# Arduino_Smart_Home_Lock.net
KiCad netlist of a schematic drawn in EAGLE
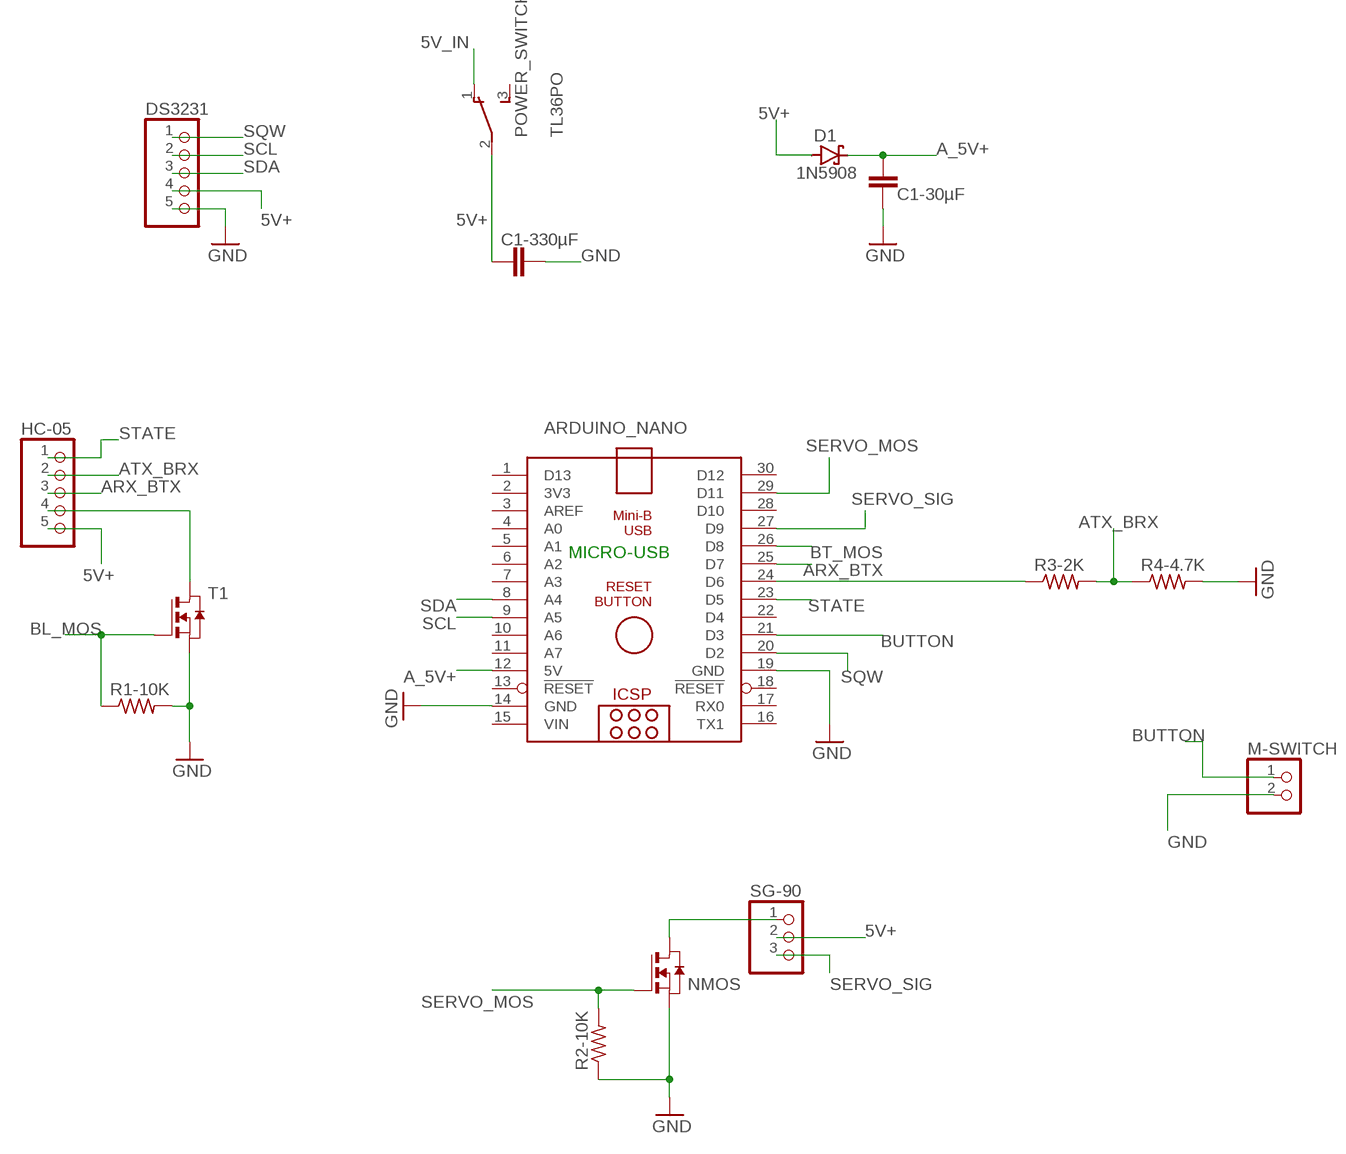
[diagram p0: schematic, sheet 1]

(export (version "E")
  (design (tool "Eeschema 10.0.6"))
  (components
    (comp (ref "ARDUINO_NANO")
      (value "ARDUINO_NANO")
      (footprint "eagle-import:ARDUINO_NANO")
      (libsource (lib "eagle-import") (part "ARDUINO_NANO"))
    )
    (comp (ref "C1-30µF")
      (value "C2.5/5")
      (footprint "eagle-import:C2.5-5")
      (libsource (lib "eagle-import") (part "C2.5/5"))
    )
    (comp (ref "C1-330µF")
      (value "C2.5/5")
      (footprint "eagle-import:C2.5-5")
      (libsource (lib "eagle-import") (part "C2.5/5"))
    )
    (comp (ref "D1")
      (value "1N5908")
      (footprint "eagle-import:C4111-15")
      (libsource (lib "eagle-import") (part "1N5908"))
    )
    (comp (ref "DS3231")
      (value "PINHD-1X55X2MM")
      (footprint "eagle-import:1_05X2MM")
      (libsource (lib "eagle-import") (part "PINHD-1X55X2MM"))
    )
    (comp (ref "HC-05")
      (value "PINHD-1X55X2MM")
      (footprint "eagle-import:1_05X2MM")
      (libsource (lib "eagle-import") (part "PINHD-1X55X2MM"))
    )
    (comp (ref "M-SWITCH")
      (value "PINHD-1X2")
      (footprint "eagle-import:1X02")
      (libsource (lib "eagle-import") (part "PINHD-1X2"))
    )
    (comp (ref "NMOS")
      (value "NMOSE3L")
      (footprint "eagle-import:E3LINE")
      (libsource (lib "eagle-import") (part "NMOSE3L"))
    )
    (comp (ref "POWER_SWITCH")
      (value "TL36PO")
      (footprint "eagle-import:TL3XPO")
      (libsource (lib "eagle-import") (part "TL36PO"))
    )
    (comp (ref "R1-10K")
      (value "R-US_0207/12")
      (footprint "eagle-import:0207_12")
      (libsource (lib "eagle-import") (part "R-US_0207/12"))
    )
    (comp (ref "R2-10K")
      (value "R-US_0207/12")
      (footprint "eagle-import:0207_12")
      (libsource (lib "eagle-import") (part "R-US_0207/12"))
    )
    (comp (ref "R3-2K")
      (value "R-US_0207/12")
      (footprint "eagle-import:0207_12")
      (libsource (lib "eagle-import") (part "R-US_0207/12"))
    )
    (comp (ref "R4-4.7K")
      (value "R-US_0207/12")
      (footprint "eagle-import:0207_12")
      (libsource (lib "eagle-import") (part "R-US_0207/12"))
    )
    (comp (ref "SG-90")
      (value "PINHD-1X3")
      (footprint "eagle-import:1X03")
      (libsource (lib "eagle-import") (part "PINHD-1X3"))
    )
    (comp (ref "T1")
      (value "NMOSE3L")
      (footprint "eagle-import:E3LINE")
      (libsource (lib "eagle-import") (part "NMOSE3L"))
    )
  )
  (nets
    (net (code "1") (name "/5V+") (class "Default")
      (node (ref "C1-330µF") (pin "1") (pinfunction "1_1") (pintype "passive"))
      (node (ref "D1") (pin "A") (pinfunction "A_A") (pintype "passive"))
      (node (ref "DS3231") (pin "4") (pinfunction "4_4") (pintype "passive"))
      (node (ref "HC-05") (pin "5") (pinfunction "5_5") (pintype "passive"))
      (node (ref "POWER_SWITCH") (pin "2") (pinfunction "P_2") (pintype "passive"))
      (node (ref "SG-90") (pin "2") (pinfunction "2_2") (pintype "passive"))
    )
    (net (code "2") (name "/5V_IN") (class "Default")
      (node (ref "POWER_SWITCH") (pin "1") (pinfunction "O_1") (pintype "passive"))
    )
    (net (code "3") (name "/ARX_BTX") (class "Default")
      (node (ref "ARDUINO_NANO") (pin "25") (pinfunction "D7_25") (pintype "bidirectional"))
      (node (ref "HC-05") (pin "3") (pinfunction "3_3") (pintype "passive"))
    )
    (net (code "4") (name "/ATX_BRX") (class "Default")
      (node (ref "HC-05") (pin "2") (pinfunction "2_2") (pintype "passive"))
      (node (ref "R3-2K") (pin "2") (pinfunction "2_2") (pintype "passive"))
      (node (ref "R4-4.7K") (pin "1") (pinfunction "1_1") (pintype "passive"))
    )
    (net (code "5") (name "/A_5V+") (class "Default")
      (node (ref "ARDUINO_NANO") (pin "12") (pinfunction "5V_12") (pintype "power_in"))
      (node (ref "C1-30µF") (pin "1") (pinfunction "1_1") (pintype "passive"))
      (node (ref "D1") (pin "C") (pinfunction "C_C") (pintype "passive"))
    )
    (net (code "6") (name "/BL_MOS") (class "Default")
      (node (ref "R1-10K") (pin "1") (pinfunction "1_1") (pintype "passive"))
      (node (ref "T1") (pin "2") (pinfunction "G_2") (pintype "passive"))
    )
    (net (code "7") (name "/BT_MOS") (class "Default")
      (node (ref "ARDUINO_NANO") (pin "26") (pinfunction "D8_26") (pintype "bidirectional"))
    )
    (net (code "8") (name "/BUTTON") (class "Default")
      (node (ref "ARDUINO_NANO") (pin "21") (pinfunction "D3_21") (pintype "bidirectional"))
      (node (ref "M-SWITCH") (pin "1") (pinfunction "1_1") (pintype "passive"))
    )
    (net (code "9") (name "/SCL") (class "Default")
      (node (ref "ARDUINO_NANO") (pin "9") (pinfunction "A5_9") (pintype "bidirectional"))
      (node (ref "DS3231") (pin "2") (pinfunction "2_2") (pintype "passive"))
    )
    (net (code "10") (name "/SDA") (class "Default")
      (node (ref "ARDUINO_NANO") (pin "8") (pinfunction "A4_8") (pintype "bidirectional"))
      (node (ref "DS3231") (pin "3") (pinfunction "3_3") (pintype "passive"))
    )
    (net (code "11") (name "/SERVO_MOS") (class "Default")
      (node (ref "ARDUINO_NANO") (pin "29") (pinfunction "D11_29") (pintype "bidirectional"))
      (node (ref "NMOS") (pin "2") (pinfunction "G_2") (pintype "passive"))
      (node (ref "R2-10K") (pin "2") (pinfunction "2_2") (pintype "passive"))
    )
    (net (code "12") (name "/SERVO_SIG") (class "Default")
      (node (ref "ARDUINO_NANO") (pin "27") (pinfunction "D9_27") (pintype "bidirectional"))
      (node (ref "SG-90") (pin "3") (pinfunction "3_3") (pintype "passive"))
    )
    (net (code "13") (name "/SQW") (class "Default")
      (node (ref "ARDUINO_NANO") (pin "20") (pinfunction "D2_20") (pintype "bidirectional"))
      (node (ref "DS3231") (pin "1") (pinfunction "1_1") (pintype "passive"))
    )
    (net (code "14") (name "/STATE") (class "Default")
      (node (ref "ARDUINO_NANO") (pin "23") (pinfunction "D5_23") (pintype "bidirectional"))
      (node (ref "HC-05") (pin "1") (pinfunction "1_1") (pintype "passive"))
    )
    (net (code "15") (name "/VIN") (class "Default")
      (node (ref "ARDUINO_NANO") (pin "15") (pinfunction "VIN_15") (pintype "power_in"))
    )
    (net (code "16") (name "GND") (class "Default")
      (node (ref "ARDUINO_NANO") (pin "14") (pinfunction "GND_14") (pintype "power_in"))
      (node (ref "ARDUINO_NANO") (pin "19") (pinfunction "GND_19") (pintype "power_in"))
      (node (ref "C1-30µF") (pin "2") (pinfunction "2_2") (pintype "passive"))
      (node (ref "C1-330µF") (pin "2") (pinfunction "2_2") (pintype "passive"))
      (node (ref "DS3231") (pin "5") (pinfunction "5_5") (pintype "passive"))
      (node (ref "M-SWITCH") (pin "2") (pinfunction "2_2") (pintype "passive"))
      (node (ref "NMOS") (pin "3") (pinfunction "S_3") (pintype "passive"))
      (node (ref "R1-10K") (pin "2") (pinfunction "2_2") (pintype "passive"))
      (node (ref "R2-10K") (pin "1") (pinfunction "1_1") (pintype "passive"))
      (node (ref "R4-4.7K") (pin "2") (pinfunction "2_2") (pintype "passive"))
      (node (ref "T1") (pin "3") (pinfunction "S_3") (pintype "passive"))
    )
    (net (code "17") (name "Net-(ARDUINO_NANO-D6)") (class "Default")
      (node (ref "ARDUINO_NANO") (pin "24") (pinfunction "D6_24") (pintype "bidirectional"))
      (node (ref "R3-2K") (pin "1") (pinfunction "1_1") (pintype "passive"))
    )
    (net (code "18") (name "Net-(NMOS-D)") (class "Default")
      (node (ref "NMOS") (pin "1") (pinfunction "D_1") (pintype "passive"))
      (node (ref "SG-90") (pin "1") (pinfunction "1_1") (pintype "passive"))
    )
    (net (code "19") (name "Net-(T1-D)") (class "Default")
      (node (ref "HC-05") (pin "4") (pinfunction "4_4") (pintype "passive"))
      (node (ref "T1") (pin "1") (pinfunction "D_1") (pintype "passive"))
    )
    (net (code "20") (name "unconnected-(ARDUINO_NANO-3V3-Pad2)") (class "Default")
      (node (ref "ARDUINO_NANO") (pin "2") (pinfunction "3V3_2") (pintype "output"))
    )
    (net (code "21") (name "unconnected-(ARDUINO_NANO-A0-Pad4)") (class "Default")
      (node (ref "ARDUINO_NANO") (pin "4") (pinfunction "A0_4") (pintype "bidirectional"))
    )
    (net (code "22") (name "unconnected-(ARDUINO_NANO-A1-Pad5)") (class "Default")
      (node (ref "ARDUINO_NANO") (pin "5") (pinfunction "A1_5") (pintype "bidirectional"))
    )
    (net (code "23") (name "unconnected-(ARDUINO_NANO-A2-Pad6)") (class "Default")
      (node (ref "ARDUINO_NANO") (pin "6") (pinfunction "A2_6") (pintype "bidirectional"))
    )
    (net (code "24") (name "unconnected-(ARDUINO_NANO-A3-Pad7)") (class "Default")
      (node (ref "ARDUINO_NANO") (pin "7") (pinfunction "A3_7") (pintype "bidirectional"))
    )
    (net (code "25") (name "unconnected-(ARDUINO_NANO-A6-Pad10)") (class "Default")
      (node (ref "ARDUINO_NANO") (pin "10") (pinfunction "A6_10") (pintype "bidirectional"))
    )
    (net (code "26") (name "unconnected-(ARDUINO_NANO-A7-Pad11)") (class "Default")
      (node (ref "ARDUINO_NANO") (pin "11") (pinfunction "A7_11") (pintype "bidirectional"))
    )
    (net (code "27") (name "unconnected-(ARDUINO_NANO-AREF-Pad3)") (class "Default")
      (node (ref "ARDUINO_NANO") (pin "3") (pinfunction "AREF_3") (pintype "input"))
    )
    (net (code "28") (name "unconnected-(ARDUINO_NANO-D4-Pad22)") (class "Default")
      (node (ref "ARDUINO_NANO") (pin "22") (pinfunction "D4_22") (pintype "bidirectional"))
    )
    (net (code "29") (name "unconnected-(ARDUINO_NANO-D10-Pad28)") (class "Default")
      (node (ref "ARDUINO_NANO") (pin "28") (pinfunction "D10_28") (pintype "bidirectional"))
    )
    (net (code "30") (name "unconnected-(ARDUINO_NANO-D12-Pad30)") (class "Default")
      (node (ref "ARDUINO_NANO") (pin "30") (pinfunction "D12_30") (pintype "bidirectional"))
    )
    (net (code "31") (name "unconnected-(ARDUINO_NANO-D13-Pad1)") (class "Default")
      (node (ref "ARDUINO_NANO") (pin "1") (pinfunction "D13_1") (pintype "bidirectional"))
    )
    (net (code "32") (name "unconnected-(ARDUINO_NANO-RX0-Pad17)") (class "Default")
      (node (ref "ARDUINO_NANO") (pin "17") (pinfunction "RX0_17") (pintype "bidirectional"))
    )
    (net (code "33") (name "unconnected-(ARDUINO_NANO-TX1-Pad16)") (class "Default")
      (node (ref "ARDUINO_NANO") (pin "16") (pinfunction "TX1_16") (pintype "bidirectional"))
    )
    (net (code "34") (name "unconnected-(ARDUINO_NANO-~{RESET}-Pad13)") (class "Default")
      (node (ref "ARDUINO_NANO") (pin "13") (pinfunction "~{RESET}_13") (pintype "input"))
    )
    (net (code "35") (name "unconnected-(ARDUINO_NANO-~{RESET}-Pad18)") (class "Default")
      (node (ref "ARDUINO_NANO") (pin "18") (pinfunction "~{RESET}_18") (pintype "input"))
    )
    (net (code "36") (name "unconnected-(POWER_SWITCH-S-Pad3)") (class "Default")
      (node (ref "POWER_SWITCH") (pin "3") (pinfunction "S_3") (pintype "passive"))
    )
  )
)
